# keyboard_schem.net
KiCad netlist of a schematic drawn in Altium Designer
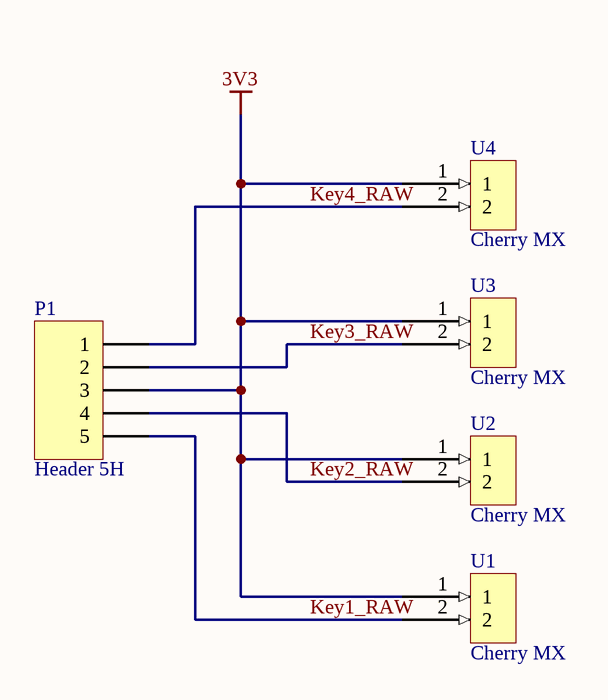
[diagram p0: keyboard_schem.SchDoc]

(export (version "E")
  (design (tool "Eeschema 10.0.6"))
  (components
    (comp (ref "P1")
      (value "Header 5H")
      (footprint "HDR1X5H")
      (description "Header, 5-Pin, Right Angle")
      (fields (field (name "PUBLISHER") "Altium Limited"))
      (libsource (lib "Miscellaneous Connectors") (part "Header 5H"))
    )
    (comp (ref "U1")
      (value "Cherry MX")
      (footprint "Cherry MX-Footprint-1")
      (description "Footprint for PCB mounted Cherry MX switch")
      (libsource (lib "Keyboard_Lib") (part "CMP-011-00015-1"))
    )
    (comp (ref "U2")
      (value "Cherry MX")
      (footprint "Cherry MX-Footprint-1")
      (description "Footprint for PCB mounted Cherry MX switch")
      (libsource (lib "Keyboard_Lib") (part "CMP-011-00015-1"))
    )
    (comp (ref "U3")
      (value "Cherry MX")
      (footprint "Cherry MX-Footprint-1")
      (description "Footprint for PCB mounted Cherry MX switch")
      (libsource (lib "Keyboard_Lib") (part "CMP-011-00015-1"))
    )
    (comp (ref "U4")
      (value "Cherry MX")
      (footprint "Cherry MX-Footprint-1")
      (description "Footprint for PCB mounted Cherry MX switch")
      (libsource (lib "Keyboard_Lib") (part "CMP-011-00015-1"))
    )
  )
  (nets
    (net (code "1") (name "/Key1_RAW") (class "Default")
      (node (ref "P1") (pin "5") (pinfunction "5_5") (pintype "passive"))
      (node (ref "U1") (pin "2") (pinfunction "2_2") (pintype "input"))
    )
    (net (code "2") (name "/Key2_RAW") (class "Default")
      (node (ref "P1") (pin "4") (pinfunction "4_4") (pintype "passive"))
      (node (ref "U2") (pin "2") (pinfunction "2_2") (pintype "input"))
    )
    (net (code "3") (name "/Key3_RAW") (class "Default")
      (node (ref "P1") (pin "2") (pinfunction "2_2") (pintype "passive"))
      (node (ref "U3") (pin "2") (pinfunction "2_2") (pintype "input"))
    )
    (net (code "4") (name "/Key4_RAW") (class "Default")
      (node (ref "P1") (pin "1") (pinfunction "1_1") (pintype "passive"))
      (node (ref "U4") (pin "2") (pinfunction "2_2") (pintype "input"))
    )
    (net (code "5") (name "3V3") (class "Default")
      (node (ref "P1") (pin "3") (pinfunction "3_3") (pintype "passive"))
      (node (ref "U1") (pin "1") (pinfunction "1_1") (pintype "input"))
      (node (ref "U2") (pin "1") (pinfunction "1_1") (pintype "input"))
      (node (ref "U3") (pin "1") (pinfunction "1_1") (pintype "input"))
      (node (ref "U4") (pin "1") (pinfunction "1_1") (pintype "input"))
    )
  )
)
